# communication.net
KiCad netlist of a schematic drawn in EAGLE
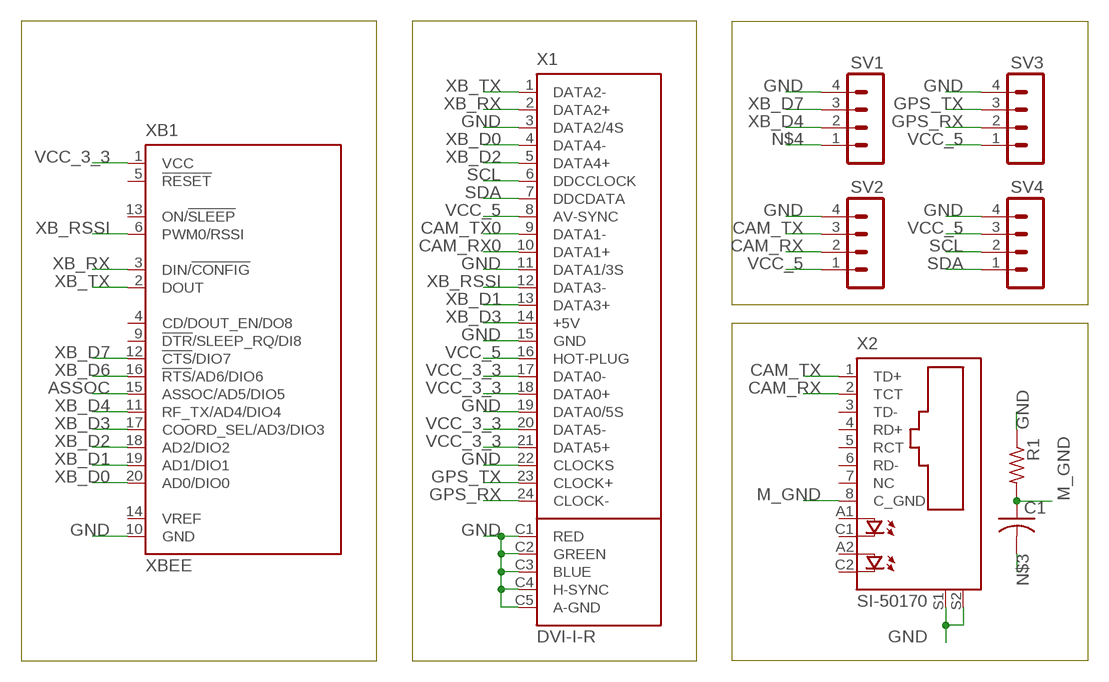
[diagram p0: schematic, sheet 1]

(export (version "E")
  (design (tool "Eeschema 10.0.6"))
  (components
    (comp (ref "C1")
      (value "C-US025-024X044")
      (footprint "eagle-import:C025-024X044")
      (libsource (lib "eagle-import") (part "C-US025-024X044"))
    )
    (comp (ref "R1")
      (value "R-US_0204/2V")
      (footprint "eagle-import:0204V")
      (libsource (lib "eagle-import") (part "R-US_0204/2V"))
    )
    (comp (ref "SV1")
      (value "MA04-1")
      (footprint "eagle-import:MA04-1")
      (libsource (lib "eagle-import") (part "MA04-1"))
    )
    (comp (ref "SV2")
      (value "MA04-1")
      (footprint "eagle-import:MA04-1")
      (libsource (lib "eagle-import") (part "MA04-1"))
    )
    (comp (ref "SV3")
      (value "MA04-1")
      (footprint "eagle-import:MA04-1")
      (libsource (lib "eagle-import") (part "MA04-1"))
    )
    (comp (ref "SV4")
      (value "MA04-1")
      (footprint "eagle-import:MA04-1")
      (libsource (lib "eagle-import") (part "MA04-1"))
    )
    (comp (ref "X1")
      (value "DVI-I-R")
      (footprint "eagle-import:DVI-I-R")
      (libsource (lib "eagle-import") (part "DVI-I-R"))
    )
    (comp (ref "X2")
      (value "SI-50170")
      (footprint "eagle-import:SI-50170")
      (libsource (lib "eagle-import") (part "SI-50170"))
    )
    (comp (ref "XB1")
      (value "XBEE")
      (footprint "eagle-import:XBEE")
      (fields (field (name "MPN") "XBP24-Z7UIT-004"))
      (libsource (lib "eagle-import") (part "XBEE"))
    )
  )
  (nets
    (net (code "1") (name "/ASSOC") (class "Default")
      (node (ref "XB1") (pin "15") (pinfunction "ASSOC/AD5/DIO5_15") (pintype "bidirectional"))
    )
    (net (code "2") (name "/CAM_RX") (class "Default")
      (node (ref "SV2") (pin "2") (pinfunction "2_2") (pintype "passive"))
      (node (ref "X2") (pin "2") (pinfunction "TCT_2") (pintype "passive"))
    )
    (net (code "3") (name "/CAM_RX0") (class "Default")
      (node (ref "X1") (pin "10") (pinfunction "DATA1+_10") (pintype "passive"))
    )
    (net (code "4") (name "/CAM_TX") (class "Default")
      (node (ref "SV2") (pin "3") (pinfunction "3_3") (pintype "passive"))
      (node (ref "X2") (pin "1") (pinfunction "TD+_1") (pintype "passive"))
    )
    (net (code "5") (name "/CAM_TX0") (class "Default")
      (node (ref "X1") (pin "9") (pinfunction "DATA1-_9") (pintype "passive"))
    )
    (net (code "6") (name "/GND") (class "Default")
      (node (ref "R1") (pin "1") (pinfunction "1_1") (pintype "passive"))
      (node (ref "SV1") (pin "4") (pinfunction "4_4") (pintype "passive"))
      (node (ref "SV2") (pin "4") (pinfunction "4_4") (pintype "passive"))
      (node (ref "SV3") (pin "4") (pinfunction "4_4") (pintype "passive"))
      (node (ref "SV4") (pin "4") (pinfunction "4_4") (pintype "passive"))
      (node (ref "X1") (pin "11") (pinfunction "DATA1/3S_11") (pintype "passive"))
      (node (ref "X1") (pin "15") (pinfunction "GND_15") (pintype "power_in"))
      (node (ref "X1") (pin "19") (pinfunction "DATA0/5S_19") (pintype "passive"))
      (node (ref "X1") (pin "22") (pinfunction "CLOCKS_22") (pintype "passive"))
      (node (ref "X1") (pin "3") (pinfunction "DATA2/4S_3") (pintype "passive"))
      (node (ref "X1") (pin "C1") (pinfunction "RED_C1") (pintype "passive"))
      (node (ref "X1") (pin "C2") (pinfunction "GREEN_C2") (pintype "passive"))
      (node (ref "X1") (pin "C3") (pinfunction "BLUE_C3") (pintype "passive"))
      (node (ref "X1") (pin "C4") (pinfunction "H-SYNC_C4") (pintype "passive"))
      (node (ref "X1") (pin "C5") (pinfunction "A-GND_C5") (pintype "power_in"))
      (node (ref "X2") (pin "S1") (pinfunction "S1_S1") (pintype "passive"))
      (node (ref "X2") (pin "S2") (pinfunction "S2_S2") (pintype "passive"))
      (node (ref "XB1") (pin "10") (pinfunction "GND_10") (pintype "power_in"))
    )
    (net (code "7") (name "/GPS_RX") (class "Default")
      (node (ref "SV3") (pin "2") (pinfunction "2_2") (pintype "passive"))
      (node (ref "X1") (pin "24") (pinfunction "CLOCK-_24") (pintype "passive"))
    )
    (net (code "8") (name "/GPS_TX") (class "Default")
      (node (ref "SV3") (pin "3") (pinfunction "3_3") (pintype "passive"))
      (node (ref "X1") (pin "23") (pinfunction "CLOCK+_23") (pintype "passive"))
    )
    (net (code "9") (name "/M_GND") (class "Default")
      (node (ref "C1") (pin "1") (pinfunction "1_1") (pintype "passive"))
      (node (ref "R1") (pin "2") (pinfunction "2_2") (pintype "passive"))
      (node (ref "X2") (pin "8") (pinfunction "C_GND_8") (pintype "passive"))
    )
    (net (code "10") (name "/N$3") (class "Default")
      (node (ref "C1") (pin "2") (pinfunction "2_2") (pintype "passive"))
    )
    (net (code "11") (name "/N$4") (class "Default")
      (node (ref "SV1") (pin "1") (pinfunction "1_1") (pintype "passive"))
    )
    (net (code "12") (name "/SCL") (class "Default")
      (node (ref "SV4") (pin "2") (pinfunction "2_2") (pintype "passive"))
      (node (ref "X1") (pin "6") (pinfunction "DDCCLOCK_6") (pintype "passive"))
    )
    (net (code "13") (name "/SDA") (class "Default")
      (node (ref "SV4") (pin "1") (pinfunction "1_1") (pintype "passive"))
      (node (ref "X1") (pin "7") (pinfunction "DDCDATA_7") (pintype "passive"))
    )
    (net (code "14") (name "/VCC_3_3") (class "Default")
      (node (ref "X1") (pin "17") (pinfunction "DATA0-_17") (pintype "passive"))
      (node (ref "X1") (pin "18") (pinfunction "DATA0+_18") (pintype "passive"))
      (node (ref "X1") (pin "20") (pinfunction "DATA5-_20") (pintype "passive"))
      (node (ref "X1") (pin "21") (pinfunction "DATA5+_21") (pintype "passive"))
      (node (ref "XB1") (pin "1") (pinfunction "VCC_1") (pintype "power_in"))
    )
    (net (code "15") (name "/VCC_5") (class "Default")
      (node (ref "SV2") (pin "1") (pinfunction "1_1") (pintype "passive"))
      (node (ref "SV3") (pin "1") (pinfunction "1_1") (pintype "passive"))
      (node (ref "SV4") (pin "3") (pinfunction "3_3") (pintype "passive"))
      (node (ref "X1") (pin "16") (pinfunction "HOT-PLUG_16") (pintype "passive"))
      (node (ref "X1") (pin "8") (pinfunction "AV-SYNC_8") (pintype "passive"))
    )
    (net (code "16") (name "/XB_D0") (class "Default")
      (node (ref "X1") (pin "4") (pinfunction "DATA4-_4") (pintype "passive"))
      (node (ref "XB1") (pin "20") (pinfunction "AD0/DIO0_20") (pintype "bidirectional"))
    )
    (net (code "17") (name "/XB_D1") (class "Default")
      (node (ref "X1") (pin "13") (pinfunction "DATA3+_13") (pintype "passive"))
      (node (ref "XB1") (pin "19") (pinfunction "AD1/DIO1_19") (pintype "bidirectional"))
    )
    (net (code "18") (name "/XB_D2") (class "Default")
      (node (ref "X1") (pin "5") (pinfunction "DATA4+_5") (pintype "passive"))
      (node (ref "XB1") (pin "18") (pinfunction "AD2/DIO2_18") (pintype "bidirectional"))
    )
    (net (code "19") (name "/XB_D3") (class "Default")
      (node (ref "X1") (pin "14") (pinfunction "+5V_14") (pintype "power_in"))
      (node (ref "XB1") (pin "17") (pinfunction "COORD_SEL/AD3/DIO3_17") (pintype "bidirectional"))
    )
    (net (code "20") (name "/XB_D4") (class "Default")
      (node (ref "SV1") (pin "2") (pinfunction "2_2") (pintype "passive"))
      (node (ref "XB1") (pin "11") (pinfunction "RF_TX/AD4/DIO4_11") (pintype "bidirectional"))
    )
    (net (code "21") (name "/XB_D6") (class "Default")
      (node (ref "XB1") (pin "16") (pinfunction "~{RTS}/AD6/DIO6_16") (pintype "bidirectional"))
    )
    (net (code "22") (name "/XB_D7") (class "Default")
      (node (ref "SV1") (pin "3") (pinfunction "3_3") (pintype "passive"))
      (node (ref "XB1") (pin "12") (pinfunction "~{CTS}/DIO7_12") (pintype "bidirectional"))
    )
    (net (code "23") (name "/XB_RSSI") (class "Default")
      (node (ref "X1") (pin "12") (pinfunction "DATA3-_12") (pintype "passive"))
      (node (ref "XB1") (pin "6") (pinfunction "PWM0/RSSI_6") (pintype "output"))
    )
    (net (code "24") (name "/XB_RX") (class "Default")
      (node (ref "X1") (pin "2") (pinfunction "DATA2+_2") (pintype "passive"))
      (node (ref "XB1") (pin "3") (pinfunction "DIN/~{CONFIG}_3") (pintype "input"))
    )
    (net (code "25") (name "/XB_TX") (class "Default")
      (node (ref "X1") (pin "1") (pinfunction "DATA2-_1") (pintype "passive"))
      (node (ref "XB1") (pin "2") (pinfunction "DOUT_2") (pintype "output"))
    )
    (net (code "26") (name "unconnected-(X2-A-PadA1)") (class "Default")
      (node (ref "X2") (pin "A1") (pinfunction "A_A1") (pintype "passive"))
    )
    (net (code "27") (name "unconnected-(X2-A1-PadA2)") (class "Default")
      (node (ref "X2") (pin "A2") (pinfunction "A1_A2") (pintype "passive"))
    )
    (net (code "28") (name "unconnected-(X2-C-PadC1)") (class "Default")
      (node (ref "X2") (pin "C1") (pinfunction "C_C1") (pintype "passive"))
    )
    (net (code "29") (name "unconnected-(X2-C1-PadC2)") (class "Default")
      (node (ref "X2") (pin "C2") (pinfunction "C1_C2") (pintype "passive"))
    )
    (net (code "30") (name "unconnected-(X2-NC-Pad7)") (class "Default")
      (node (ref "X2") (pin "7") (pinfunction "NC_7") (pintype "passive"))
    )
    (net (code "31") (name "unconnected-(X2-RCT-Pad5)") (class "Default")
      (node (ref "X2") (pin "5") (pinfunction "RCT_5") (pintype "passive"))
    )
    (net (code "32") (name "unconnected-(X2-RD+-Pad4)") (class "Default")
      (node (ref "X2") (pin "4") (pinfunction "RD+_4") (pintype "passive"))
    )
    (net (code "33") (name "unconnected-(X2-RD--Pad6)") (class "Default")
      (node (ref "X2") (pin "6") (pinfunction "RD-_6") (pintype "passive"))
    )
    (net (code "34") (name "unconnected-(X2-TD--Pad3)") (class "Default")
      (node (ref "X2") (pin "3") (pinfunction "TD-_3") (pintype "passive"))
    )
    (net (code "35") (name "unconnected-(XB1-CD{slash}DOUT_EN{slash}DO8-Pad4)") (class "Default")
      (node (ref "XB1") (pin "4") (pinfunction "CD/DOUT_EN/DO8_4") (pintype "output"))
    )
    (net (code "36") (name "unconnected-(XB1-ON{slash}~{SLEEP}-Pad13)") (class "Default")
      (node (ref "XB1") (pin "13") (pinfunction "ON/~{SLEEP}_13") (pintype "output"))
    )
    (net (code "37") (name "unconnected-(XB1-VREF-Pad14)") (class "Default")
      (node (ref "XB1") (pin "14") (pinfunction "VREF_14") (pintype "input"))
    )
    (net (code "38") (name "unconnected-(XB1-~{DTR}{slash}SLEEP_RQ{slash}DI8-Pad9)") (class "Default")
      (node (ref "XB1") (pin "9") (pinfunction "~{DTR}/SLEEP_RQ/DI8_9") (pintype "bidirectional"))
    )
    (net (code "39") (name "unconnected-(XB1-~{RESET}-Pad5)") (class "Default")
      (node (ref "XB1") (pin "5") (pinfunction "~{RESET}_5") (pintype "input"))
    )
  )
)
